# Adapter_Light.net
KiCad netlist of a schematic drawn in EAGLE
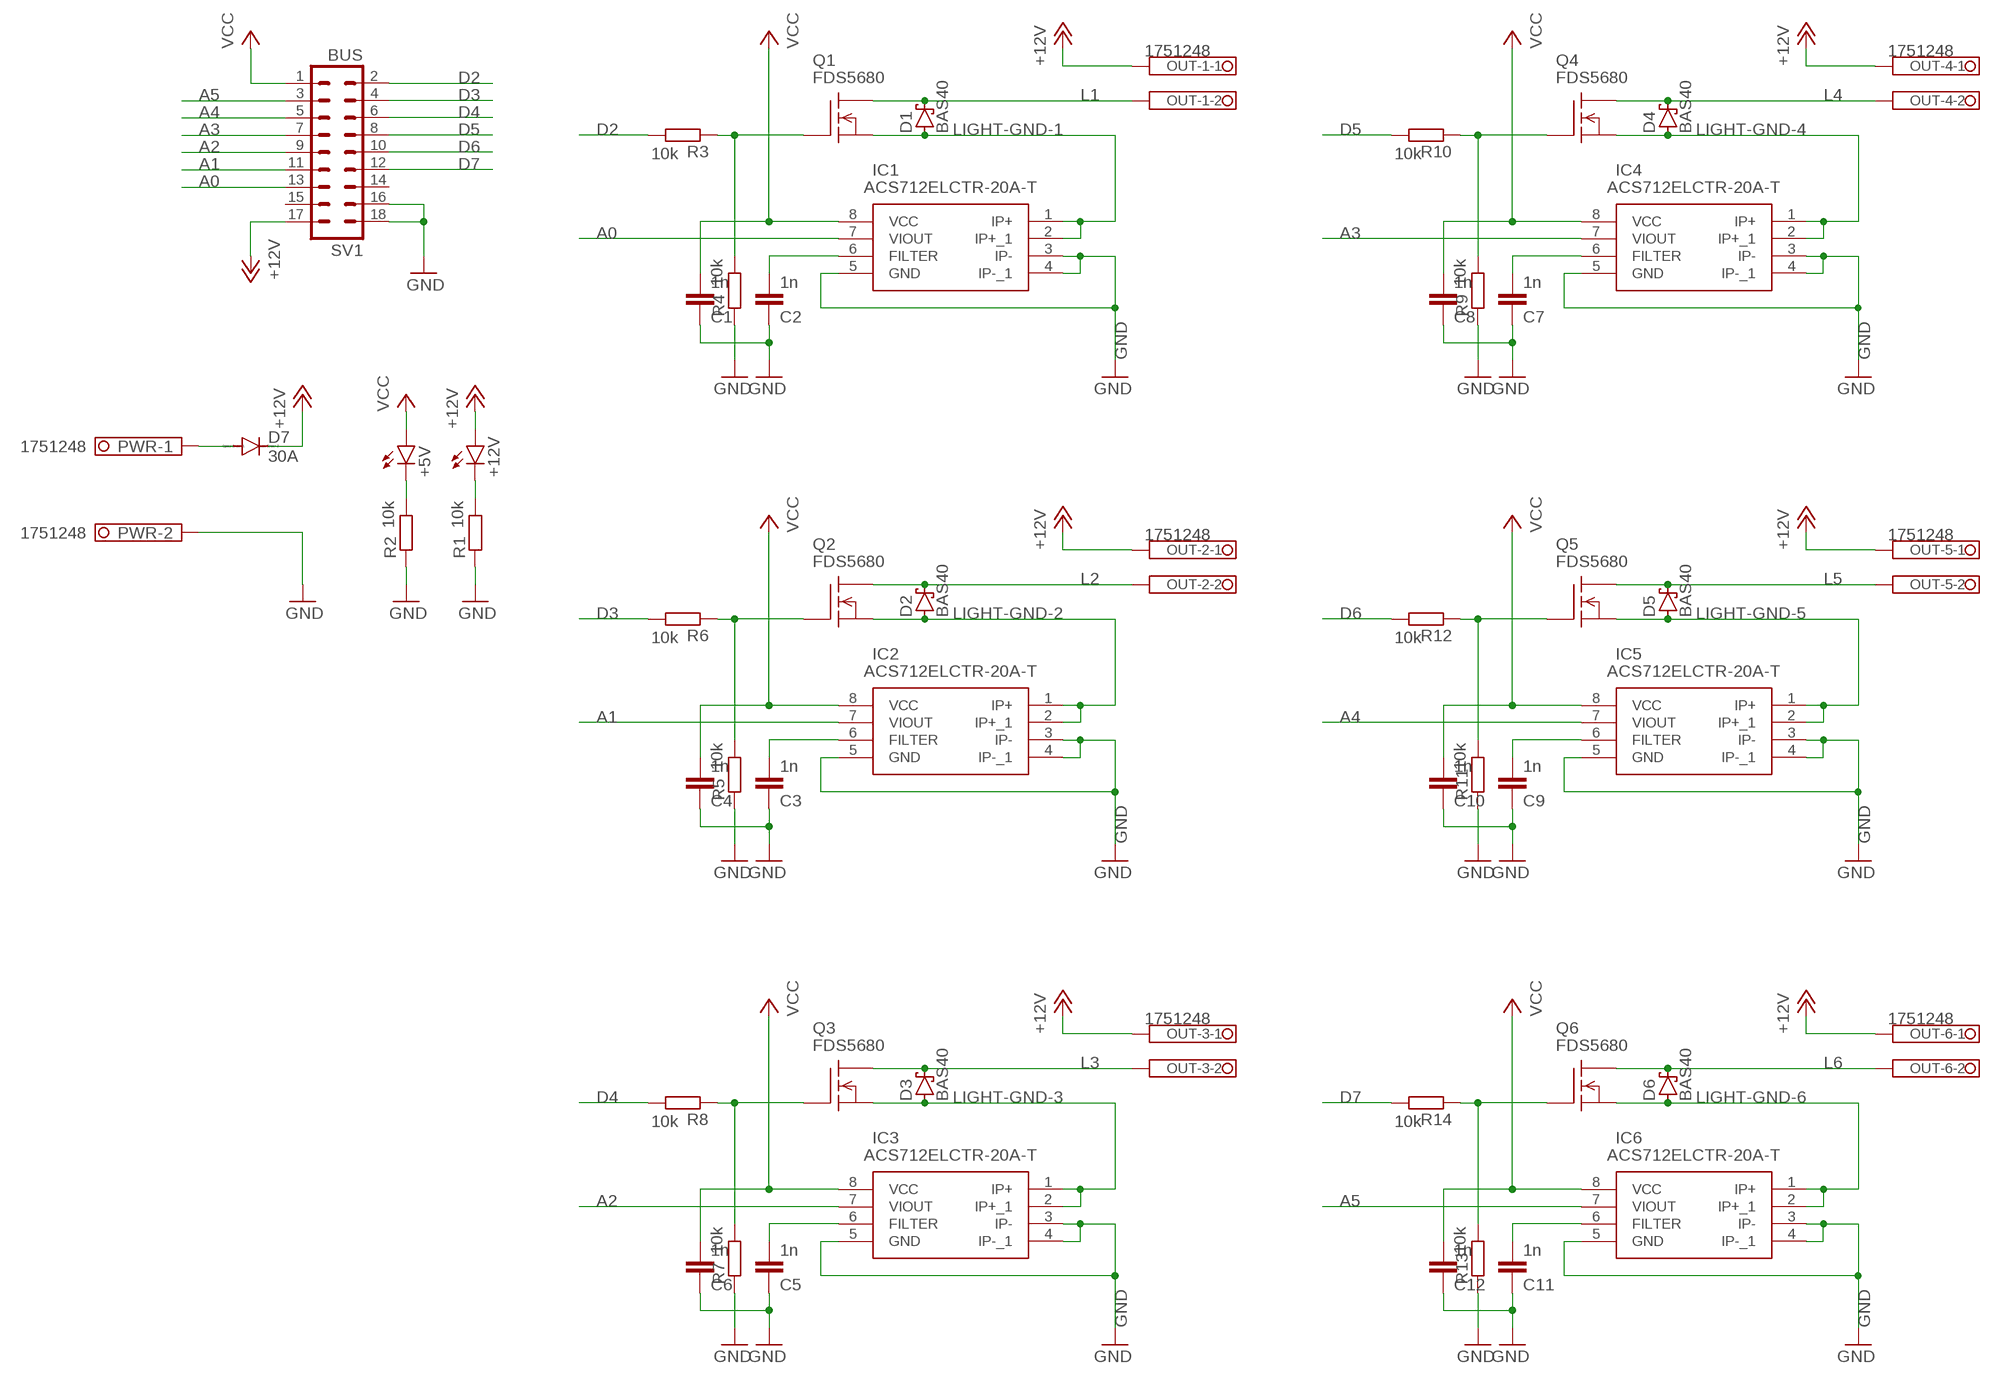
[diagram p0: schematic, sheet 1]

(export (version "E")
  (design (tool "Eeschema 10.0.6"))
  (components
    (comp (ref "+5V")
      (value "LED3MM")
      (footprint "eagle-import:LED3MM")
      (libsource (lib "eagle-import") (part "LED3MM"))
    )
    (comp (ref "+12V")
      (value "LED3MM")
      (footprint "eagle-import:LED3MM")
      (libsource (lib "eagle-import") (part "LED3MM"))
    )
    (comp (ref "C1")
      (value "1n")
      (footprint "eagle-import:C0402K")
      (libsource (lib "eagle-import") (part "C-EUC0402K"))
    )
    (comp (ref "C2")
      (value "1n")
      (footprint "eagle-import:C0402K")
      (libsource (lib "eagle-import") (part "C-EUC0402K"))
    )
    (comp (ref "C3")
      (value "1n")
      (footprint "eagle-import:C0402K")
      (libsource (lib "eagle-import") (part "C-EUC0402K"))
    )
    (comp (ref "C4")
      (value "1n")
      (footprint "eagle-import:C0402K")
      (libsource (lib "eagle-import") (part "C-EUC0402K"))
    )
    (comp (ref "C5")
      (value "1n")
      (footprint "eagle-import:C0402K")
      (libsource (lib "eagle-import") (part "C-EUC0402K"))
    )
    (comp (ref "C6")
      (value "1n")
      (footprint "eagle-import:C0402K")
      (libsource (lib "eagle-import") (part "C-EUC0402K"))
    )
    (comp (ref "C7")
      (value "1n")
      (footprint "eagle-import:C0402K")
      (libsource (lib "eagle-import") (part "C-EUC0402K"))
    )
    (comp (ref "C8")
      (value "1n")
      (footprint "eagle-import:C0402K")
      (libsource (lib "eagle-import") (part "C-EUC0402K"))
    )
    (comp (ref "C9")
      (value "1n")
      (footprint "eagle-import:C0402K")
      (libsource (lib "eagle-import") (part "C-EUC0402K"))
    )
    (comp (ref "C10")
      (value "1n")
      (footprint "eagle-import:C0402K")
      (libsource (lib "eagle-import") (part "C-EUC0402K"))
    )
    (comp (ref "C11")
      (value "1n")
      (footprint "eagle-import:C0402K")
      (libsource (lib "eagle-import") (part "C-EUC0402K"))
    )
    (comp (ref "C12")
      (value "1n")
      (footprint "eagle-import:C0402K")
      (libsource (lib "eagle-import") (part "C-EUC0402K"))
    )
    (comp (ref "D1")
      (value "BAS40")
      (footprint "eagle-import:SOT23")
      (libsource (lib "eagle-import") (part "BAS40"))
    )
    (comp (ref "D2")
      (value "BAS40")
      (footprint "eagle-import:SOT23")
      (libsource (lib "eagle-import") (part "BAS40"))
    )
    (comp (ref "D3")
      (value "BAS40")
      (footprint "eagle-import:SOT23")
      (libsource (lib "eagle-import") (part "BAS40"))
    )
    (comp (ref "D4")
      (value "BAS40")
      (footprint "eagle-import:SOT23")
      (libsource (lib "eagle-import") (part "BAS40"))
    )
    (comp (ref "D5")
      (value "BAS40")
      (footprint "eagle-import:SOT23")
      (libsource (lib "eagle-import") (part "BAS40"))
    )
    (comp (ref "D6")
      (value "BAS40")
      (footprint "eagle-import:SOT23")
      (libsource (lib "eagle-import") (part "BAS40"))
    )
    (comp (ref "D7")
      (value "30A")
      (footprint "eagle-import:DO15-12")
      (libsource (lib "eagle-import") (part "DIODE-DO15-12"))
    )
    (comp (ref "IC1")
      (value "ACS712ELCTR-20A-T")
      (footprint "eagle-import:SOIC127P600X175-8N")
      (fields (field (name "RS_PART_NUMBER") "6807135P"))
      (libsource (lib "eagle-import") (part "ACS712ELCTR-20A-T"))
    )
    (comp (ref "IC2")
      (value "ACS712ELCTR-20A-T")
      (footprint "eagle-import:SOIC127P600X175-8N")
      (fields (field (name "RS_PART_NUMBER") "6807135P"))
      (libsource (lib "eagle-import") (part "ACS712ELCTR-20A-T"))
    )
    (comp (ref "IC3")
      (value "ACS712ELCTR-20A-T")
      (footprint "eagle-import:SOIC127P600X175-8N")
      (fields (field (name "RS_PART_NUMBER") "6807135P"))
      (libsource (lib "eagle-import") (part "ACS712ELCTR-20A-T"))
    )
    (comp (ref "IC4")
      (value "ACS712ELCTR-20A-T")
      (footprint "eagle-import:SOIC127P600X175-8N")
      (fields (field (name "RS_PART_NUMBER") "6807135P"))
      (libsource (lib "eagle-import") (part "ACS712ELCTR-20A-T"))
    )
    (comp (ref "IC5")
      (value "ACS712ELCTR-20A-T")
      (footprint "eagle-import:SOIC127P600X175-8N")
      (fields (field (name "RS_PART_NUMBER") "6807135P"))
      (libsource (lib "eagle-import") (part "ACS712ELCTR-20A-T"))
    )
    (comp (ref "IC6")
      (value "ACS712ELCTR-20A-T")
      (footprint "eagle-import:SOIC127P600X175-8N")
      (fields (field (name "RS_PART_NUMBER") "6807135P"))
      (libsource (lib "eagle-import") (part "ACS712ELCTR-20A-T"))
    )
    (comp (ref "OUT-1")
      (value "1751248")
      (footprint "eagle-import:1751248")
      (libsource (lib "eagle-import") (part "1751248"))
    )
    (comp (ref "OUT-2")
      (value "1751248")
      (footprint "eagle-import:1751248")
      (libsource (lib "eagle-import") (part "1751248"))
    )
    (comp (ref "OUT-3")
      (value "1751248")
      (footprint "eagle-import:1751248")
      (libsource (lib "eagle-import") (part "1751248"))
    )
    (comp (ref "OUT-4")
      (value "1751248")
      (footprint "eagle-import:1751248")
      (libsource (lib "eagle-import") (part "1751248"))
    )
    (comp (ref "OUT-5")
      (value "1751248")
      (footprint "eagle-import:1751248")
      (libsource (lib "eagle-import") (part "1751248"))
    )
    (comp (ref "OUT-6")
      (value "1751248")
      (footprint "eagle-import:1751248")
      (libsource (lib "eagle-import") (part "1751248"))
    )
    (comp (ref "PWR")
      (value "1751248")
      (footprint "eagle-import:1751248")
      (libsource (lib "eagle-import") (part "1751248"))
    )
    (comp (ref "Q1")
      (value "FDS5680")
      (footprint "eagle-import:SO-8")
      (libsource (lib "eagle-import") (part "FDS5680"))
    )
    (comp (ref "Q2")
      (value "FDS5680")
      (footprint "eagle-import:SO-8")
      (libsource (lib "eagle-import") (part "FDS5680"))
    )
    (comp (ref "Q3")
      (value "FDS5680")
      (footprint "eagle-import:SO-8")
      (libsource (lib "eagle-import") (part "FDS5680"))
    )
    (comp (ref "Q4")
      (value "FDS5680")
      (footprint "eagle-import:SO-8")
      (libsource (lib "eagle-import") (part "FDS5680"))
    )
    (comp (ref "Q5")
      (value "FDS5680")
      (footprint "eagle-import:SO-8")
      (libsource (lib "eagle-import") (part "FDS5680"))
    )
    (comp (ref "Q6")
      (value "FDS5680")
      (footprint "eagle-import:SO-8")
      (libsource (lib "eagle-import") (part "FDS5680"))
    )
    (comp (ref "R1")
      (value "10k")
      (footprint "eagle-import:MINI_MELF-0102W")
      (libsource (lib "eagle-import") (part "R-EU_MELF0102W"))
    )
    (comp (ref "R2")
      (value "10k")
      (footprint "eagle-import:MINI_MELF-0102W")
      (libsource (lib "eagle-import") (part "R-EU_MELF0102W"))
    )
    (comp (ref "R3")
      (value "10k")
      (footprint "eagle-import:MINI_MELF-0102W")
      (libsource (lib "eagle-import") (part "R-EU_MELF0102W"))
    )
    (comp (ref "R4")
      (value "10k")
      (footprint "eagle-import:MINI_MELF-0102W")
      (libsource (lib "eagle-import") (part "R-EU_MELF0102W"))
    )
    (comp (ref "R5")
      (value "10k")
      (footprint "eagle-import:MINI_MELF-0102W")
      (libsource (lib "eagle-import") (part "R-EU_MELF0102W"))
    )
    (comp (ref "R6")
      (value "10k")
      (footprint "eagle-import:MINI_MELF-0102W")
      (libsource (lib "eagle-import") (part "R-EU_MELF0102W"))
    )
    (comp (ref "R7")
      (value "10k")
      (footprint "eagle-import:MINI_MELF-0102W")
      (libsource (lib "eagle-import") (part "R-EU_MELF0102W"))
    )
    (comp (ref "R8")
      (value "10k")
      (footprint "eagle-import:MINI_MELF-0102W")
      (libsource (lib "eagle-import") (part "R-EU_MELF0102W"))
    )
    (comp (ref "R9")
      (value "10k")
      (footprint "eagle-import:MINI_MELF-0102W")
      (libsource (lib "eagle-import") (part "R-EU_MELF0102W"))
    )
    (comp (ref "R10")
      (value "10k")
      (footprint "eagle-import:MINI_MELF-0102W")
      (libsource (lib "eagle-import") (part "R-EU_MELF0102W"))
    )
    (comp (ref "R11")
      (value "10k")
      (footprint "eagle-import:MINI_MELF-0102W")
      (libsource (lib "eagle-import") (part "R-EU_MELF0102W"))
    )
    (comp (ref "R12")
      (value "10k")
      (footprint "eagle-import:MINI_MELF-0102W")
      (libsource (lib "eagle-import") (part "R-EU_MELF0102W"))
    )
    (comp (ref "R13")
      (value "10k")
      (footprint "eagle-import:MINI_MELF-0102W")
      (libsource (lib "eagle-import") (part "R-EU_MELF0102W"))
    )
    (comp (ref "R14")
      (value "10k")
      (footprint "eagle-import:MINI_MELF-0102W")
      (libsource (lib "eagle-import") (part "R-EU_MELF0102W"))
    )
    (comp (ref "SV1")
      (value "BUS")
      (footprint "eagle-import:MA09-2")
      (libsource (lib "eagle-import") (part "MA09-2"))
    )
  )
  (nets
    (net (code "1") (name "+12V") (class "Default")
      (node (ref "+12V") (pin "A") (pinfunction "A_A") (pintype "passive"))
      (node (ref "D7") (pin "C") (pinfunction "C_C") (pintype "passive"))
      (node (ref "OUT-1") (pin "1") (pinfunction "K_1") (pintype "passive"))
      (node (ref "OUT-2") (pin "1") (pinfunction "K_1") (pintype "passive"))
      (node (ref "OUT-3") (pin "1") (pinfunction "K_1") (pintype "passive"))
      (node (ref "OUT-4") (pin "1") (pinfunction "K_1") (pintype "passive"))
      (node (ref "OUT-5") (pin "1") (pinfunction "K_1") (pintype "passive"))
      (node (ref "OUT-6") (pin "1") (pinfunction "K_1") (pintype "passive"))
      (node (ref "SV1") (pin "17") (pinfunction "17_17") (pintype "passive"))
    )
    (net (code "2") (name "A0") (class "Default")
      (node (ref "IC1") (pin "7") (pinfunction "VIOUT_7") (pintype "bidirectional"))
      (node (ref "SV1") (pin "13") (pinfunction "13_13") (pintype "passive"))
    )
    (net (code "3") (name "A1") (class "Default")
      (node (ref "IC2") (pin "7") (pinfunction "VIOUT_7") (pintype "bidirectional"))
      (node (ref "SV1") (pin "11") (pinfunction "11_11") (pintype "passive"))
    )
    (net (code "4") (name "A2") (class "Default")
      (node (ref "IC3") (pin "7") (pinfunction "VIOUT_7") (pintype "bidirectional"))
      (node (ref "SV1") (pin "9") (pinfunction "9_9") (pintype "passive"))
    )
    (net (code "5") (name "A3") (class "Default")
      (node (ref "IC4") (pin "7") (pinfunction "VIOUT_7") (pintype "bidirectional"))
      (node (ref "SV1") (pin "7") (pinfunction "7_7") (pintype "passive"))
    )
    (net (code "6") (name "A4") (class "Default")
      (node (ref "IC5") (pin "7") (pinfunction "VIOUT_7") (pintype "bidirectional"))
      (node (ref "SV1") (pin "5") (pinfunction "5_5") (pintype "passive"))
    )
    (net (code "7") (name "A5") (class "Default")
      (node (ref "IC6") (pin "7") (pinfunction "VIOUT_7") (pintype "bidirectional"))
      (node (ref "SV1") (pin "3") (pinfunction "3_3") (pintype "passive"))
    )
    (net (code "8") (name "D2") (class "Default")
      (node (ref "R3") (pin "2") (pinfunction "2_2") (pintype "passive"))
      (node (ref "SV1") (pin "2") (pinfunction "2_2") (pintype "passive"))
    )
    (net (code "9") (name "D3") (class "Default")
      (node (ref "R6") (pin "2") (pinfunction "2_2") (pintype "passive"))
      (node (ref "SV1") (pin "4") (pinfunction "4_4") (pintype "passive"))
    )
    (net (code "10") (name "D4") (class "Default")
      (node (ref "R8") (pin "2") (pinfunction "2_2") (pintype "passive"))
      (node (ref "SV1") (pin "6") (pinfunction "6_6") (pintype "passive"))
    )
    (net (code "11") (name "D5") (class "Default")
      (node (ref "R10") (pin "2") (pinfunction "2_2") (pintype "passive"))
      (node (ref "SV1") (pin "8") (pinfunction "8_8") (pintype "passive"))
    )
    (net (code "12") (name "D6") (class "Default")
      (node (ref "R12") (pin "2") (pinfunction "2_2") (pintype "passive"))
      (node (ref "SV1") (pin "10") (pinfunction "10_10") (pintype "passive"))
    )
    (net (code "13") (name "D7") (class "Default")
      (node (ref "R14") (pin "2") (pinfunction "2_2") (pintype "passive"))
      (node (ref "SV1") (pin "12") (pinfunction "12_12") (pintype "passive"))
    )
    (net (code "14") (name "GND") (class "Default")
      (node (ref "C1") (pin "1") (pinfunction "1_1") (pintype "passive"))
      (node (ref "C10") (pin "1") (pinfunction "1_1") (pintype "passive"))
      (node (ref "C11") (pin "1") (pinfunction "1_1") (pintype "passive"))
      (node (ref "C12") (pin "1") (pinfunction "1_1") (pintype "passive"))
      (node (ref "C2") (pin "1") (pinfunction "1_1") (pintype "passive"))
      (node (ref "C3") (pin "1") (pinfunction "1_1") (pintype "passive"))
      (node (ref "C4") (pin "1") (pinfunction "1_1") (pintype "passive"))
      (node (ref "C5") (pin "1") (pinfunction "1_1") (pintype "passive"))
      (node (ref "C6") (pin "1") (pinfunction "1_1") (pintype "passive"))
      (node (ref "C7") (pin "1") (pinfunction "1_1") (pintype "passive"))
      (node (ref "C8") (pin "1") (pinfunction "1_1") (pintype "passive"))
      (node (ref "C9") (pin "1") (pinfunction "1_1") (pintype "passive"))
      (node (ref "IC1") (pin "3") (pinfunction "IP-_3") (pintype "bidirectional"))
      (node (ref "IC1") (pin "4") (pinfunction "IP-_1_4") (pintype "bidirectional"))
      (node (ref "IC1") (pin "5") (pinfunction "GND_5") (pintype "power_in"))
      (node (ref "IC2") (pin "3") (pinfunction "IP-_3") (pintype "bidirectional"))
      (node (ref "IC2") (pin "4") (pinfunction "IP-_1_4") (pintype "bidirectional"))
      (node (ref "IC2") (pin "5") (pinfunction "GND_5") (pintype "power_in"))
      (node (ref "IC3") (pin "3") (pinfunction "IP-_3") (pintype "bidirectional"))
      (node (ref "IC3") (pin "4") (pinfunction "IP-_1_4") (pintype "bidirectional"))
      (node (ref "IC3") (pin "5") (pinfunction "GND_5") (pintype "power_in"))
      (node (ref "IC4") (pin "3") (pinfunction "IP-_3") (pintype "bidirectional"))
      (node (ref "IC4") (pin "4") (pinfunction "IP-_1_4") (pintype "bidirectional"))
      (node (ref "IC4") (pin "5") (pinfunction "GND_5") (pintype "power_in"))
      (node (ref "IC5") (pin "3") (pinfunction "IP-_3") (pintype "bidirectional"))
      (node (ref "IC5") (pin "4") (pinfunction "IP-_1_4") (pintype "bidirectional"))
      (node (ref "IC5") (pin "5") (pinfunction "GND_5") (pintype "power_in"))
      (node (ref "IC6") (pin "3") (pinfunction "IP-_3") (pintype "bidirectional"))
      (node (ref "IC6") (pin "4") (pinfunction "IP-_1_4") (pintype "bidirectional"))
      (node (ref "IC6") (pin "5") (pinfunction "GND_5") (pintype "power_in"))
      (node (ref "PWR") (pin "2") (pinfunction "K_2") (pintype "passive"))
      (node (ref "R1") (pin "1") (pinfunction "1_1") (pintype "passive"))
      (node (ref "R11") (pin "1") (pinfunction "1_1") (pintype "passive"))
      (node (ref "R13") (pin "1") (pinfunction "1_1") (pintype "passive"))
      (node (ref "R2") (pin "1") (pinfunction "1_1") (pintype "passive"))
      (node (ref "R4") (pin "1") (pinfunction "1_1") (pintype "passive"))
      (node (ref "R5") (pin "1") (pinfunction "1_1") (pintype "passive"))
      (node (ref "R7") (pin "1") (pinfunction "1_1") (pintype "passive"))
      (node (ref "R9") (pin "1") (pinfunction "1_1") (pintype "passive"))
      (node (ref "SV1") (pin "16") (pinfunction "16_16") (pintype "passive"))
      (node (ref "SV1") (pin "18") (pinfunction "18_18") (pintype "passive"))
    )
    (net (code "15") (name "L1") (class "Default")
      (node (ref "D1") (pin "3") (pinfunction "C_3") (pintype "passive"))
      (node (ref "OUT-1") (pin "2") (pinfunction "K_2") (pintype "passive"))
      (node (ref "Q1") (pin "5") (pinfunction "D_5") (pintype "passive"))
      (node (ref "Q1") (pin "6") (pinfunction "D_6") (pintype "passive"))
      (node (ref "Q1") (pin "7") (pinfunction "D_7") (pintype "passive"))
      (node (ref "Q1") (pin "8") (pinfunction "D_8") (pintype "passive"))
    )
    (net (code "16") (name "L2") (class "Default")
      (node (ref "D2") (pin "3") (pinfunction "C_3") (pintype "passive"))
      (node (ref "OUT-2") (pin "2") (pinfunction "K_2") (pintype "passive"))
      (node (ref "Q2") (pin "5") (pinfunction "D_5") (pintype "passive"))
      (node (ref "Q2") (pin "6") (pinfunction "D_6") (pintype "passive"))
      (node (ref "Q2") (pin "7") (pinfunction "D_7") (pintype "passive"))
      (node (ref "Q2") (pin "8") (pinfunction "D_8") (pintype "passive"))
    )
    (net (code "17") (name "L3") (class "Default")
      (node (ref "D3") (pin "3") (pinfunction "C_3") (pintype "passive"))
      (node (ref "OUT-3") (pin "2") (pinfunction "K_2") (pintype "passive"))
      (node (ref "Q3") (pin "5") (pinfunction "D_5") (pintype "passive"))
      (node (ref "Q3") (pin "6") (pinfunction "D_6") (pintype "passive"))
      (node (ref "Q3") (pin "7") (pinfunction "D_7") (pintype "passive"))
      (node (ref "Q3") (pin "8") (pinfunction "D_8") (pintype "passive"))
    )
    (net (code "18") (name "L4") (class "Default")
      (node (ref "D4") (pin "3") (pinfunction "C_3") (pintype "passive"))
      (node (ref "OUT-4") (pin "2") (pinfunction "K_2") (pintype "passive"))
      (node (ref "Q4") (pin "5") (pinfunction "D_5") (pintype "passive"))
      (node (ref "Q4") (pin "6") (pinfunction "D_6") (pintype "passive"))
      (node (ref "Q4") (pin "7") (pinfunction "D_7") (pintype "passive"))
      (node (ref "Q4") (pin "8") (pinfunction "D_8") (pintype "passive"))
    )
    (net (code "19") (name "L5") (class "Default")
      (node (ref "D5") (pin "3") (pinfunction "C_3") (pintype "passive"))
      (node (ref "OUT-5") (pin "2") (pinfunction "K_2") (pintype "passive"))
      (node (ref "Q5") (pin "5") (pinfunction "D_5") (pintype "passive"))
      (node (ref "Q5") (pin "6") (pinfunction "D_6") (pintype "passive"))
      (node (ref "Q5") (pin "7") (pinfunction "D_7") (pintype "passive"))
      (node (ref "Q5") (pin "8") (pinfunction "D_8") (pintype "passive"))
    )
    (net (code "20") (name "L6") (class "Default")
      (node (ref "D6") (pin "3") (pinfunction "C_3") (pintype "passive"))
      (node (ref "OUT-6") (pin "2") (pinfunction "K_2") (pintype "passive"))
      (node (ref "Q6") (pin "5") (pinfunction "D_5") (pintype "passive"))
      (node (ref "Q6") (pin "6") (pinfunction "D_6") (pintype "passive"))
      (node (ref "Q6") (pin "7") (pinfunction "D_7") (pintype "passive"))
      (node (ref "Q6") (pin "8") (pinfunction "D_8") (pintype "passive"))
    )
    (net (code "21") (name "LIGHT-GND-1") (class "Default")
      (node (ref "D1") (pin "1") (pinfunction "A_1") (pintype "passive"))
      (node (ref "IC1") (pin "1") (pinfunction "IP+_1") (pintype "bidirectional"))
      (node (ref "IC1") (pin "2") (pinfunction "IP+_1_2") (pintype "bidirectional"))
      (node (ref "Q1") (pin "1") (pinfunction "S_1") (pintype "passive"))
      (node (ref "Q1") (pin "2") (pinfunction "S_2") (pintype "passive"))
      (node (ref "Q1") (pin "3") (pinfunction "S_3") (pintype "passive"))
    )
    (net (code "22") (name "LIGHT-GND-2") (class "Default")
      (node (ref "D2") (pin "1") (pinfunction "A_1") (pintype "passive"))
      (node (ref "IC2") (pin "1") (pinfunction "IP+_1") (pintype "bidirectional"))
      (node (ref "IC2") (pin "2") (pinfunction "IP+_1_2") (pintype "bidirectional"))
      (node (ref "Q2") (pin "1") (pinfunction "S_1") (pintype "passive"))
      (node (ref "Q2") (pin "2") (pinfunction "S_2") (pintype "passive"))
      (node (ref "Q2") (pin "3") (pinfunction "S_3") (pintype "passive"))
    )
    (net (code "23") (name "LIGHT-GND-3") (class "Default")
      (node (ref "D3") (pin "1") (pinfunction "A_1") (pintype "passive"))
      (node (ref "IC3") (pin "1") (pinfunction "IP+_1") (pintype "bidirectional"))
      (node (ref "IC3") (pin "2") (pinfunction "IP+_1_2") (pintype "bidirectional"))
      (node (ref "Q3") (pin "1") (pinfunction "S_1") (pintype "passive"))
      (node (ref "Q3") (pin "2") (pinfunction "S_2") (pintype "passive"))
      (node (ref "Q3") (pin "3") (pinfunction "S_3") (pintype "passive"))
    )
    (net (code "24") (name "LIGHT-GND-4") (class "Default")
      (node (ref "D4") (pin "1") (pinfunction "A_1") (pintype "passive"))
      (node (ref "IC4") (pin "1") (pinfunction "IP+_1") (pintype "bidirectional"))
      (node (ref "IC4") (pin "2") (pinfunction "IP+_1_2") (pintype "bidirectional"))
      (node (ref "Q4") (pin "1") (pinfunction "S_1") (pintype "passive"))
      (node (ref "Q4") (pin "2") (pinfunction "S_2") (pintype "passive"))
      (node (ref "Q4") (pin "3") (pinfunction "S_3") (pintype "passive"))
    )
    (net (code "25") (name "LIGHT-GND-5") (class "Default")
      (node (ref "D5") (pin "1") (pinfunction "A_1") (pintype "passive"))
      (node (ref "IC5") (pin "1") (pinfunction "IP+_1") (pintype "bidirectional"))
      (node (ref "IC5") (pin "2") (pinfunction "IP+_1_2") (pintype "bidirectional"))
      (node (ref "Q5") (pin "1") (pinfunction "S_1") (pintype "passive"))
      (node (ref "Q5") (pin "2") (pinfunction "S_2") (pintype "passive"))
      (node (ref "Q5") (pin "3") (pinfunction "S_3") (pintype "passive"))
    )
    (net (code "26") (name "LIGHT-GND-6") (class "Default")
      (node (ref "D6") (pin "1") (pinfunction "A_1") (pintype "passive"))
      (node (ref "IC6") (pin "1") (pinfunction "IP+_1") (pintype "bidirectional"))
      (node (ref "IC6") (pin "2") (pinfunction "IP+_1_2") (pintype "bidirectional"))
      (node (ref "Q6") (pin "1") (pinfunction "S_1") (pintype "passive"))
      (node (ref "Q6") (pin "2") (pinfunction "S_2") (pintype "passive"))
      (node (ref "Q6") (pin "3") (pinfunction "S_3") (pintype "passive"))
    )
    (net (code "27") (name "Net-(+5V-C)") (class "Default")
      (node (ref "+5V") (pin "K") (pinfunction "C_K") (pintype "passive"))
      (node (ref "R2") (pin "2") (pinfunction "2_2") (pintype "passive"))
    )
    (net (code "28") (name "Net-(+12V-C)") (class "Default")
      (node (ref "+12V") (pin "K") (pinfunction "C_K") (pintype "passive"))
      (node (ref "R1") (pin "2") (pinfunction "2_2") (pintype "passive"))
    )
    (net (code "29") (name "Net-(IC1-FILTER)") (class "Default")
      (node (ref "C2") (pin "2") (pinfunction "2_2") (pintype "passive"))
      (node (ref "IC1") (pin "6") (pinfunction "FILTER_6") (pintype "bidirectional"))
    )
    (net (code "30") (name "Net-(IC2-FILTER)") (class "Default")
      (node (ref "C3") (pin "2") (pinfunction "2_2") (pintype "passive"))
      (node (ref "IC2") (pin "6") (pinfunction "FILTER_6") (pintype "bidirectional"))
    )
    (net (code "31") (name "Net-(IC3-FILTER)") (class "Default")
      (node (ref "C5") (pin "2") (pinfunction "2_2") (pintype "passive"))
      (node (ref "IC3") (pin "6") (pinfunction "FILTER_6") (pintype "bidirectional"))
    )
    (net (code "32") (name "Net-(IC4-FILTER)") (class "Default")
      (node (ref "C7") (pin "2") (pinfunction "2_2") (pintype "passive"))
      (node (ref "IC4") (pin "6") (pinfunction "FILTER_6") (pintype "bidirectional"))
    )
    (net (code "33") (name "Net-(IC5-FILTER)") (class "Default")
      (node (ref "C9") (pin "2") (pinfunction "2_2") (pintype "passive"))
      (node (ref "IC5") (pin "6") (pinfunction "FILTER_6") (pintype "bidirectional"))
    )
    (net (code "34") (name "Net-(IC6-FILTER)") (class "Default")
      (node (ref "C11") (pin "2") (pinfunction "2_2") (pintype "passive"))
      (node (ref "IC6") (pin "6") (pinfunction "FILTER_6") (pintype "bidirectional"))
    )
    (net (code "35") (name "Net-(PWRA-K)") (class "Default")
      (node (ref "D7") (pin "A") (pinfunction "A_A") (pintype "passive"))
      (node (ref "PWR") (pin "1") (pinfunction "K_1") (pintype "passive"))
    )
    (net (code "36") (name "Net-(Q1-G)") (class "Default")
      (node (ref "Q1") (pin "4") (pinfunction "G_4") (pintype "passive"))
      (node (ref "R3") (pin "1") (pinfunction "1_1") (pintype "passive"))
      (node (ref "R4") (pin "2") (pinfunction "2_2") (pintype "passive"))
    )
    (net (code "37") (name "Net-(Q2-G)") (class "Default")
      (node (ref "Q2") (pin "4") (pinfunction "G_4") (pintype "passive"))
      (node (ref "R5") (pin "2") (pinfunction "2_2") (pintype "passive"))
      (node (ref "R6") (pin "1") (pinfunction "1_1") (pintype "passive"))
    )
    (net (code "38") (name "Net-(Q3-G)") (class "Default")
      (node (ref "Q3") (pin "4") (pinfunction "G_4") (pintype "passive"))
      (node (ref "R7") (pin "2") (pinfunction "2_2") (pintype "passive"))
      (node (ref "R8") (pin "1") (pinfunction "1_1") (pintype "passive"))
    )
    (net (code "39") (name "Net-(Q4-G)") (class "Default")
      (node (ref "Q4") (pin "4") (pinfunction "G_4") (pintype "passive"))
      (node (ref "R10") (pin "1") (pinfunction "1_1") (pintype "passive"))
      (node (ref "R9") (pin "2") (pinfunction "2_2") (pintype "passive"))
    )
    (net (code "40") (name "Net-(Q5-G)") (class "Default")
      (node (ref "Q5") (pin "4") (pinfunction "G_4") (pintype "passive"))
      (node (ref "R11") (pin "2") (pinfunction "2_2") (pintype "passive"))
      (node (ref "R12") (pin "1") (pinfunction "1_1") (pintype "passive"))
    )
    (net (code "41") (name "Net-(Q6-G)") (class "Default")
      (node (ref "Q6") (pin "4") (pinfunction "G_4") (pintype "passive"))
      (node (ref "R13") (pin "2") (pinfunction "2_2") (pintype "passive"))
      (node (ref "R14") (pin "1") (pinfunction "1_1") (pintype "passive"))
    )
    (net (code "42") (name "VCC") (class "Default")
      (node (ref "+5V") (pin "A") (pinfunction "A_A") (pintype "passive"))
      (node (ref "C1") (pin "2") (pinfunction "2_2") (pintype "passive"))
      (node (ref "C10") (pin "2") (pinfunction "2_2") (pintype "passive"))
      (node (ref "C12") (pin "2") (pinfunction "2_2") (pintype "passive"))
      (node (ref "C4") (pin "2") (pinfunction "2_2") (pintype "passive"))
      (node (ref "C6") (pin "2") (pinfunction "2_2") (pintype "passive"))
      (node (ref "C8") (pin "2") (pinfunction "2_2") (pintype "passive"))
      (node (ref "IC1") (pin "8") (pinfunction "VCC_8") (pintype "power_in"))
      (node (ref "IC2") (pin "8") (pinfunction "VCC_8") (pintype "power_in"))
      (node (ref "IC3") (pin "8") (pinfunction "VCC_8") (pintype "power_in"))
      (node (ref "IC4") (pin "8") (pinfunction "VCC_8") (pintype "power_in"))
      (node (ref "IC5") (pin "8") (pinfunction "VCC_8") (pintype "power_in"))
      (node (ref "IC6") (pin "8") (pinfunction "VCC_8") (pintype "power_in"))
      (node (ref "SV1") (pin "1") (pinfunction "1_1") (pintype "passive"))
    )
    (net (code "43") (name "unconnected-(SV1-Pad14)") (class "Default")
      (node (ref "SV1") (pin "14") (pinfunction "14_14") (pintype "passive"))
    )
    (net (code "44") (name "unconnected-(SV1-Pad15)") (class "Default")
      (node (ref "SV1") (pin "15") (pinfunction "15_15") (pintype "passive"))
    )
  )
)
